# SCH_Life-Counter_2024-05-18.net
KiCad netlist of a schematic drawn in EasyEDA
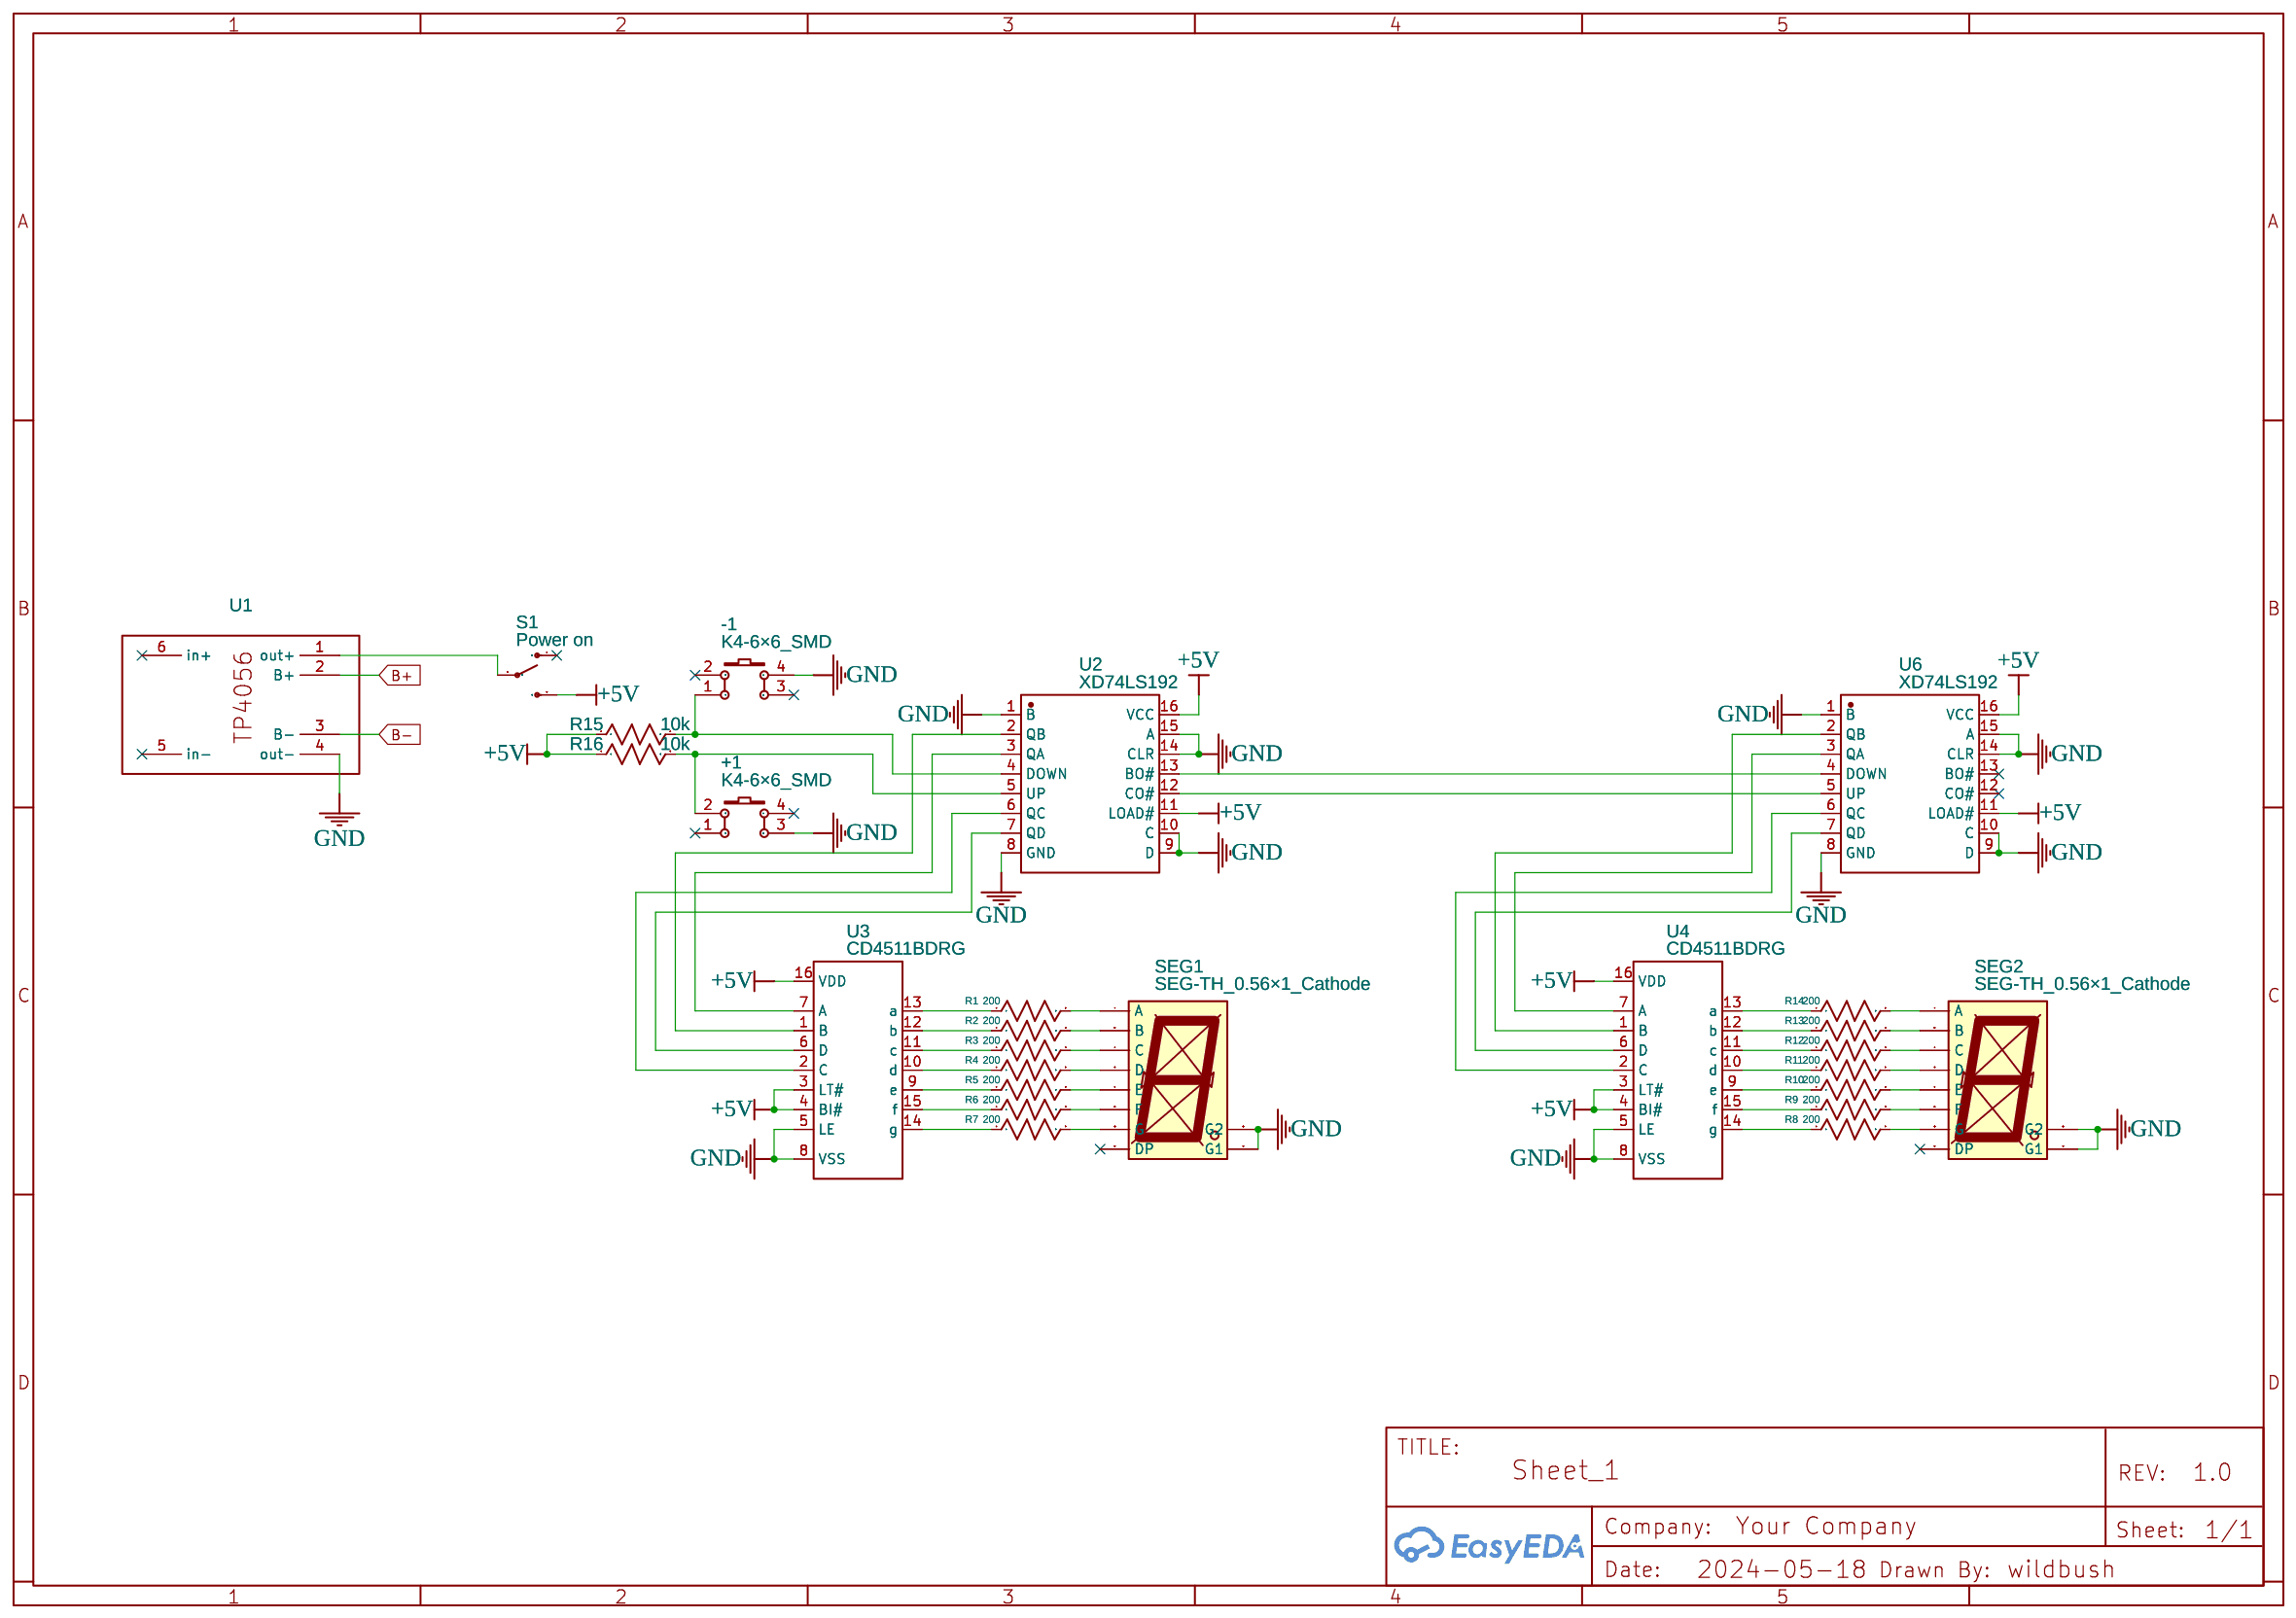
[diagram p0: schematic sheet]

(export (version "E")
  (design (tool "Eeschema 10.0.6"))
  (components
    (comp (ref "+1")
      (value "K4-6×6_SMD")
      (fields (field (name "Manufacturer Part") "K2-6639SP-D4SC-04") (field (name "Manufacturer") "韩国韩荣"))
      (libsource (lib "") (part "K4-6×6_SMD"))
    )
    (comp (ref "-1")
      (value "K4-6×6_SMD")
      (fields (field (name "Manufacturer Part") "K2-6639SP-D4SC-04") (field (name "Manufacturer") "韩国韩荣"))
      (libsource (lib "") (part "K4-6×6_SMD_1"))
    )
    (comp (ref "R1") (value "200") (libsource (lib "") (part "R_AXIAL-0.3_US")))
    (comp (ref "R2") (value "200") (libsource (lib "") (part "R_AXIAL-0.3_US")))
    (comp (ref "R3") (value "200") (libsource (lib "") (part "R_AXIAL-0.3_US")))
    (comp (ref "R4") (value "200") (libsource (lib "") (part "R_AXIAL-0.3_US")))
    (comp (ref "R5") (value "200") (libsource (lib "") (part "R_AXIAL-0.3_US")))
    (comp (ref "R6") (value "200") (libsource (lib "") (part "R_AXIAL-0.3_US")))
    (comp (ref "R7") (value "200") (libsource (lib "") (part "R_AXIAL-0.3_US")))
    (comp (ref "R8") (value "200") (libsource (lib "") (part "R_AXIAL-0.3_US")))
    (comp (ref "R9") (value "200") (libsource (lib "") (part "R_AXIAL-0.3_US")))
    (comp (ref "R10") (value "200") (libsource (lib "") (part "R_AXIAL-0.3_US")))
    (comp (ref "R11") (value "200") (libsource (lib "") (part "R_AXIAL-0.3_US")))
    (comp (ref "R12") (value "200") (libsource (lib "") (part "R_AXIAL-0.3_US")))
    (comp (ref "R13") (value "200") (libsource (lib "") (part "R_AXIAL-0.3_US")))
    (comp (ref "R14") (value "200") (libsource (lib "") (part "R_AXIAL-0.3_US")))
    (comp (ref "R15") (value "10k") (libsource (lib "") (part "R_AXIAL-0.3_US")))
    (comp (ref "R16") (value "10k") (libsource (lib "") (part "R_AXIAL-0.3_US")))
    (comp (ref "S1") (value "Power on") (libsource (lib "") (part "SWITCH-SPDT")))
    (comp (ref "SEG1")
      (value "SEG-TH_0.56×1_Cathode")
      (fields (field (name "Manufacturer") "志浩"))
      (libsource (lib "") (part "SEG-TH_0.56×1_Cathode"))
    )
    (comp (ref "SEG2")
      (value "SEG-TH_0.56×1_Cathode")
      (fields (field (name "Manufacturer") "志浩"))
      (libsource (lib "") (part "SEG-TH_0.56×1_Cathode"))
    )
    (comp (ref "U1") (value "NO") (libsource (lib "") (part "TP4056")))
    (comp (ref "U2")
      (value "XD74LS192")
      (fields (field (name "Manufacturer") "XINLUDA(信路达)"))
      (libsource (lib "") (part "XD74LS192"))
    )
    (comp (ref "U3")
      (value "CD4511BDRG")
      (fields (field (name "Manufacturer") "HGC(深圳汉芯)"))
      (libsource (lib "") (part "CD4511BDRG"))
    )
    (comp (ref "U4")
      (value "CD4511BDRG")
      (fields (field (name "Manufacturer") "HGC(深圳汉芯)"))
      (libsource (lib "") (part "CD4511BDRG"))
    )
    (comp (ref "U6")
      (value "XD74LS192")
      (fields (field (name "Manufacturer") "XINLUDA(信路达)"))
      (libsource (lib "") (part "XD74LS192"))
    )
  )
  (nets
    (net (code "1") (name "+5V") (class "Default")
      (node (ref "R15") (pin "1") (pinfunction "1_1") (pintype "unspecified"))
      (node (ref "R16") (pin "1") (pinfunction "1_1") (pintype "unspecified"))
      (node (ref "S1") (pin "3") (pinfunction "S_3") (pintype "unspecified"))
      (node (ref "U2") (pin "11") (pinfunction "LOAD#_11") (pintype "unspecified"))
      (node (ref "U2") (pin "16") (pinfunction "VCC_16") (pintype "unspecified"))
      (node (ref "U3") (pin "16") (pinfunction "VDD_16") (pintype "unspecified"))
      (node (ref "U3") (pin "3") (pinfunction "LT#_3") (pintype "unspecified"))
      (node (ref "U3") (pin "4") (pinfunction "BI#_4") (pintype "unspecified"))
      (node (ref "U4") (pin "16") (pinfunction "VDD_16") (pintype "unspecified"))
      (node (ref "U4") (pin "3") (pinfunction "LT#_3") (pintype "unspecified"))
      (node (ref "U4") (pin "4") (pinfunction "BI#_4") (pintype "unspecified"))
      (node (ref "U6") (pin "11") (pinfunction "LOAD#_11") (pintype "unspecified"))
      (node (ref "U6") (pin "16") (pinfunction "VCC_16") (pintype "unspecified"))
    )
    (net (code "2") (name "B+") (class "Default")
      (node (ref "U1") (pin "2") (pinfunction "B+_2") (pintype "unspecified"))
    )
    (net (code "3") (name "B-") (class "Default")
      (node (ref "U1") (pin "3") (pinfunction "B-_3") (pintype "unspecified"))
    )
    (net (code "4") (name "GND") (class "Default")
      (node (ref "+1") (pin "3") (pinfunction "3_3") (pintype "unspecified"))
      (node (ref "-1") (pin "4") (pinfunction "4_4") (pintype "unspecified"))
      (node (ref "SEG1") (pin "3") (pinfunction "G1_3") (pintype "unspecified"))
      (node (ref "SEG1") (pin "8") (pinfunction "G2_8") (pintype "unspecified"))
      (node (ref "SEG2") (pin "3") (pinfunction "G1_3") (pintype "unspecified"))
      (node (ref "SEG2") (pin "8") (pinfunction "G2_8") (pintype "unspecified"))
      (node (ref "U1") (pin "4") (pinfunction "out-_4") (pintype "unspecified"))
      (node (ref "U2") (pin "1") (pinfunction "B_1") (pintype "unspecified"))
      (node (ref "U2") (pin "10") (pinfunction "C_10") (pintype "unspecified"))
      (node (ref "U2") (pin "14") (pinfunction "CLR_14") (pintype "unspecified"))
      (node (ref "U2") (pin "15") (pinfunction "A_15") (pintype "unspecified"))
      (node (ref "U2") (pin "8") (pinfunction "GND_8") (pintype "unspecified"))
      (node (ref "U2") (pin "9") (pinfunction "D_9") (pintype "unspecified"))
      (node (ref "U3") (pin "5") (pinfunction "LE_5") (pintype "unspecified"))
      (node (ref "U3") (pin "8") (pinfunction "VSS_8") (pintype "unspecified"))
      (node (ref "U4") (pin "5") (pinfunction "LE_5") (pintype "unspecified"))
      (node (ref "U4") (pin "8") (pinfunction "VSS_8") (pintype "unspecified"))
      (node (ref "U6") (pin "1") (pinfunction "B_1") (pintype "unspecified"))
      (node (ref "U6") (pin "10") (pinfunction "C_10") (pintype "unspecified"))
      (node (ref "U6") (pin "14") (pinfunction "CLR_14") (pintype "unspecified"))
      (node (ref "U6") (pin "15") (pinfunction "A_15") (pintype "unspecified"))
      (node (ref "U6") (pin "8") (pinfunction "GND_8") (pintype "unspecified"))
      (node (ref "U6") (pin "9") (pinfunction "D_9") (pintype "unspecified"))
    )
    (net (code "5") (name "Net-(S1-P)") (class "Default")
      (node (ref "S1") (pin "2") (pinfunction "P_2") (pintype "unspecified"))
      (node (ref "U1") (pin "1") (pinfunction "out+_1") (pintype "unspecified"))
    )
    (net (code "6") (name "Net-(SEG1-A)") (class "Default")
      (node (ref "R1") (pin "2") (pinfunction "2_2") (pintype "unspecified"))
      (node (ref "SEG1") (pin "7") (pinfunction "A_7") (pintype "unspecified"))
    )
    (net (code "7") (name "Net-(SEG1-B)") (class "Default")
      (node (ref "R2") (pin "2") (pinfunction "2_2") (pintype "unspecified"))
      (node (ref "SEG1") (pin "6") (pinfunction "B_6") (pintype "unspecified"))
    )
    (net (code "8") (name "Net-(SEG1-C)") (class "Default")
      (node (ref "R3") (pin "2") (pinfunction "2_2") (pintype "unspecified"))
      (node (ref "SEG1") (pin "4") (pinfunction "C_4") (pintype "unspecified"))
    )
    (net (code "9") (name "Net-(SEG1-D)") (class "Default")
      (node (ref "R4") (pin "2") (pinfunction "2_2") (pintype "unspecified"))
      (node (ref "SEG1") (pin "2") (pinfunction "D_2") (pintype "unspecified"))
    )
    (net (code "10") (name "Net-(SEG1-E)") (class "Default")
      (node (ref "R5") (pin "2") (pinfunction "2_2") (pintype "unspecified"))
      (node (ref "SEG1") (pin "1") (pinfunction "E_1") (pintype "unspecified"))
    )
    (net (code "11") (name "Net-(SEG1-F)") (class "Default")
      (node (ref "R6") (pin "2") (pinfunction "2_2") (pintype "unspecified"))
      (node (ref "SEG1") (pin "9") (pinfunction "F_9") (pintype "unspecified"))
    )
    (net (code "12") (name "Net-(SEG1-G)") (class "Default")
      (node (ref "R7") (pin "2") (pinfunction "2_2") (pintype "unspecified"))
      (node (ref "SEG1") (pin "10") (pinfunction "G_10") (pintype "unspecified"))
    )
    (net (code "13") (name "Net-(SEG2-A)") (class "Default")
      (node (ref "R14") (pin "2") (pinfunction "2_2") (pintype "unspecified"))
      (node (ref "SEG2") (pin "7") (pinfunction "A_7") (pintype "unspecified"))
    )
    (net (code "14") (name "Net-(SEG2-B)") (class "Default")
      (node (ref "R13") (pin "2") (pinfunction "2_2") (pintype "unspecified"))
      (node (ref "SEG2") (pin "6") (pinfunction "B_6") (pintype "unspecified"))
    )
    (net (code "15") (name "Net-(SEG2-C)") (class "Default")
      (node (ref "R12") (pin "2") (pinfunction "2_2") (pintype "unspecified"))
      (node (ref "SEG2") (pin "4") (pinfunction "C_4") (pintype "unspecified"))
    )
    (net (code "16") (name "Net-(SEG2-D)") (class "Default")
      (node (ref "R11") (pin "2") (pinfunction "2_2") (pintype "unspecified"))
      (node (ref "SEG2") (pin "2") (pinfunction "D_2") (pintype "unspecified"))
    )
    (net (code "17") (name "Net-(SEG2-E)") (class "Default")
      (node (ref "R10") (pin "2") (pinfunction "2_2") (pintype "unspecified"))
      (node (ref "SEG2") (pin "1") (pinfunction "E_1") (pintype "unspecified"))
    )
    (net (code "18") (name "Net-(SEG2-F)") (class "Default")
      (node (ref "R9") (pin "2") (pinfunction "2_2") (pintype "unspecified"))
      (node (ref "SEG2") (pin "9") (pinfunction "F_9") (pintype "unspecified"))
    )
    (net (code "19") (name "Net-(SEG2-G)") (class "Default")
      (node (ref "R8") (pin "2") (pinfunction "2_2") (pintype "unspecified"))
      (node (ref "SEG2") (pin "10") (pinfunction "G_10") (pintype "unspecified"))
    )
    (net (code "20") (name "Net-(U2-BO#)") (class "Default")
      (node (ref "U2") (pin "13") (pinfunction "BO#_13") (pintype "unspecified"))
      (node (ref "U6") (pin "4") (pinfunction "DOWN_4") (pintype "unspecified"))
    )
    (net (code "21") (name "Net-(U2-CO#)") (class "Default")
      (node (ref "U2") (pin "12") (pinfunction "CO#_12") (pintype "unspecified"))
      (node (ref "U6") (pin "5") (pinfunction "UP_5") (pintype "unspecified"))
    )
    (net (code "22") (name "Net-(U2-DOWN)") (class "Default")
      (node (ref "-1") (pin "1") (pinfunction "1_1") (pintype "unspecified"))
      (node (ref "R15") (pin "2") (pinfunction "2_2") (pintype "unspecified"))
      (node (ref "U2") (pin "4") (pinfunction "DOWN_4") (pintype "unspecified"))
    )
    (net (code "23") (name "Net-(U2-QA)") (class "Default")
      (node (ref "U2") (pin "3") (pinfunction "QA_3") (pintype "unspecified"))
      (node (ref "U3") (pin "7") (pinfunction "A_7") (pintype "unspecified"))
    )
    (net (code "24") (name "Net-(U2-QB)") (class "Default")
      (node (ref "U2") (pin "2") (pinfunction "QB_2") (pintype "unspecified"))
      (node (ref "U3") (pin "1") (pinfunction "B_1") (pintype "unspecified"))
    )
    (net (code "25") (name "Net-(U2-QC)") (class "Default")
      (node (ref "U2") (pin "6") (pinfunction "QC_6") (pintype "unspecified"))
      (node (ref "U3") (pin "2") (pinfunction "C_2") (pintype "unspecified"))
    )
    (net (code "26") (name "Net-(U2-QD)") (class "Default")
      (node (ref "U2") (pin "7") (pinfunction "QD_7") (pintype "unspecified"))
      (node (ref "U3") (pin "6") (pinfunction "D_6") (pintype "unspecified"))
    )
    (net (code "27") (name "Net-(U2-UP)") (class "Default")
      (node (ref "+1") (pin "2") (pinfunction "2_2") (pintype "unspecified"))
      (node (ref "R16") (pin "2") (pinfunction "2_2") (pintype "unspecified"))
      (node (ref "U2") (pin "5") (pinfunction "UP_5") (pintype "unspecified"))
    )
    (net (code "28") (name "Net-(U3-a)") (class "Default")
      (node (ref "R1") (pin "1") (pinfunction "1_1") (pintype "unspecified"))
      (node (ref "U3") (pin "13") (pinfunction "a_13") (pintype "unspecified"))
    )
    (net (code "29") (name "Net-(U3-b)") (class "Default")
      (node (ref "R2") (pin "1") (pinfunction "1_1") (pintype "unspecified"))
      (node (ref "U3") (pin "12") (pinfunction "b_12") (pintype "unspecified"))
    )
    (net (code "30") (name "Net-(U3-c)") (class "Default")
      (node (ref "R3") (pin "1") (pinfunction "1_1") (pintype "unspecified"))
      (node (ref "U3") (pin "11") (pinfunction "c_11") (pintype "unspecified"))
    )
    (net (code "31") (name "Net-(U3-d)") (class "Default")
      (node (ref "R4") (pin "1") (pinfunction "1_1") (pintype "unspecified"))
      (node (ref "U3") (pin "10") (pinfunction "d_10") (pintype "unspecified"))
    )
    (net (code "32") (name "Net-(U3-e)") (class "Default")
      (node (ref "R5") (pin "1") (pinfunction "1_1") (pintype "unspecified"))
      (node (ref "U3") (pin "9") (pinfunction "e_9") (pintype "unspecified"))
    )
    (net (code "33") (name "Net-(U3-f)") (class "Default")
      (node (ref "R6") (pin "1") (pinfunction "1_1") (pintype "unspecified"))
      (node (ref "U3") (pin "15") (pinfunction "f_15") (pintype "unspecified"))
    )
    (net (code "34") (name "Net-(U3-g)") (class "Default")
      (node (ref "R7") (pin "1") (pinfunction "1_1") (pintype "unspecified"))
      (node (ref "U3") (pin "14") (pinfunction "g_14") (pintype "unspecified"))
    )
    (net (code "35") (name "Net-(U4-A)") (class "Default")
      (node (ref "U4") (pin "7") (pinfunction "A_7") (pintype "unspecified"))
      (node (ref "U6") (pin "3") (pinfunction "QA_3") (pintype "unspecified"))
    )
    (net (code "36") (name "Net-(U4-B)") (class "Default")
      (node (ref "U4") (pin "1") (pinfunction "B_1") (pintype "unspecified"))
      (node (ref "U6") (pin "2") (pinfunction "QB_2") (pintype "unspecified"))
    )
    (net (code "37") (name "Net-(U4-C)") (class "Default")
      (node (ref "U4") (pin "2") (pinfunction "C_2") (pintype "unspecified"))
      (node (ref "U6") (pin "6") (pinfunction "QC_6") (pintype "unspecified"))
    )
    (net (code "38") (name "Net-(U4-D)") (class "Default")
      (node (ref "U4") (pin "6") (pinfunction "D_6") (pintype "unspecified"))
      (node (ref "U6") (pin "7") (pinfunction "QD_7") (pintype "unspecified"))
    )
    (net (code "39") (name "Net-(U4-a)") (class "Default")
      (node (ref "R14") (pin "1") (pinfunction "1_1") (pintype "unspecified"))
      (node (ref "U4") (pin "13") (pinfunction "a_13") (pintype "unspecified"))
    )
    (net (code "40") (name "Net-(U4-b)") (class "Default")
      (node (ref "R13") (pin "1") (pinfunction "1_1") (pintype "unspecified"))
      (node (ref "U4") (pin "12") (pinfunction "b_12") (pintype "unspecified"))
    )
    (net (code "41") (name "Net-(U4-c)") (class "Default")
      (node (ref "R12") (pin "1") (pinfunction "1_1") (pintype "unspecified"))
      (node (ref "U4") (pin "11") (pinfunction "c_11") (pintype "unspecified"))
    )
    (net (code "42") (name "Net-(U4-d)") (class "Default")
      (node (ref "R11") (pin "1") (pinfunction "1_1") (pintype "unspecified"))
      (node (ref "U4") (pin "10") (pinfunction "d_10") (pintype "unspecified"))
    )
    (net (code "43") (name "Net-(U4-e)") (class "Default")
      (node (ref "R10") (pin "1") (pinfunction "1_1") (pintype "unspecified"))
      (node (ref "U4") (pin "9") (pinfunction "e_9") (pintype "unspecified"))
    )
    (net (code "44") (name "Net-(U4-f)") (class "Default")
      (node (ref "R9") (pin "1") (pinfunction "1_1") (pintype "unspecified"))
      (node (ref "U4") (pin "15") (pinfunction "f_15") (pintype "unspecified"))
    )
    (net (code "45") (name "Net-(U4-g)") (class "Default")
      (node (ref "R8") (pin "1") (pinfunction "1_1") (pintype "unspecified"))
      (node (ref "U4") (pin "14") (pinfunction "g_14") (pintype "unspecified"))
    )
    (net (code "46") (name "unconnected-(+1-Pad1)") (class "Default")
      (node (ref "+1") (pin "1") (pinfunction "1_1") (pintype "unspecified+no_connect"))
    )
    (net (code "47") (name "unconnected-(+1-Pad4)") (class "Default")
      (node (ref "+1") (pin "4") (pinfunction "4_4") (pintype "unspecified+no_connect"))
    )
    (net (code "48") (name "unconnected-(-1-Pad2)") (class "Default")
      (node (ref "-1") (pin "2") (pinfunction "2_2") (pintype "unspecified+no_connect"))
    )
    (net (code "49") (name "unconnected-(-1-Pad3)") (class "Default")
      (node (ref "-1") (pin "3") (pinfunction "3_3") (pintype "unspecified+no_connect"))
    )
    (net (code "50") (name "unconnected-(S1-O-Pad1)") (class "Default")
      (node (ref "S1") (pin "1") (pinfunction "O_1") (pintype "unspecified+no_connect"))
    )
    (net (code "51") (name "unconnected-(SEG1-DP-Pad5)") (class "Default")
      (node (ref "SEG1") (pin "5") (pinfunction "DP_5") (pintype "unspecified+no_connect"))
    )
    (net (code "52") (name "unconnected-(SEG2-DP-Pad5)") (class "Default")
      (node (ref "SEG2") (pin "5") (pinfunction "DP_5") (pintype "unspecified+no_connect"))
    )
    (net (code "53") (name "unconnected-(U1-in+-Pad6)") (class "Default")
      (node (ref "U1") (pin "6") (pinfunction "in+_6") (pintype "unspecified+no_connect"))
    )
    (net (code "54") (name "unconnected-(U1-in--Pad5)") (class "Default")
      (node (ref "U1") (pin "5") (pinfunction "in-_5") (pintype "unspecified+no_connect"))
    )
    (net (code "55") (name "unconnected-(U6-BO#-Pad13)") (class "Default")
      (node (ref "U6") (pin "13") (pinfunction "BO#_13") (pintype "unspecified+no_connect"))
    )
    (net (code "56") (name "unconnected-(U6-CO#-Pad12)") (class "Default")
      (node (ref "U6") (pin "12") (pinfunction "CO#_12") (pintype "unspecified+no_connect"))
    )
  )
)
